# Float24.net
KiCad netlist of a schematic drawn in Altium Designer
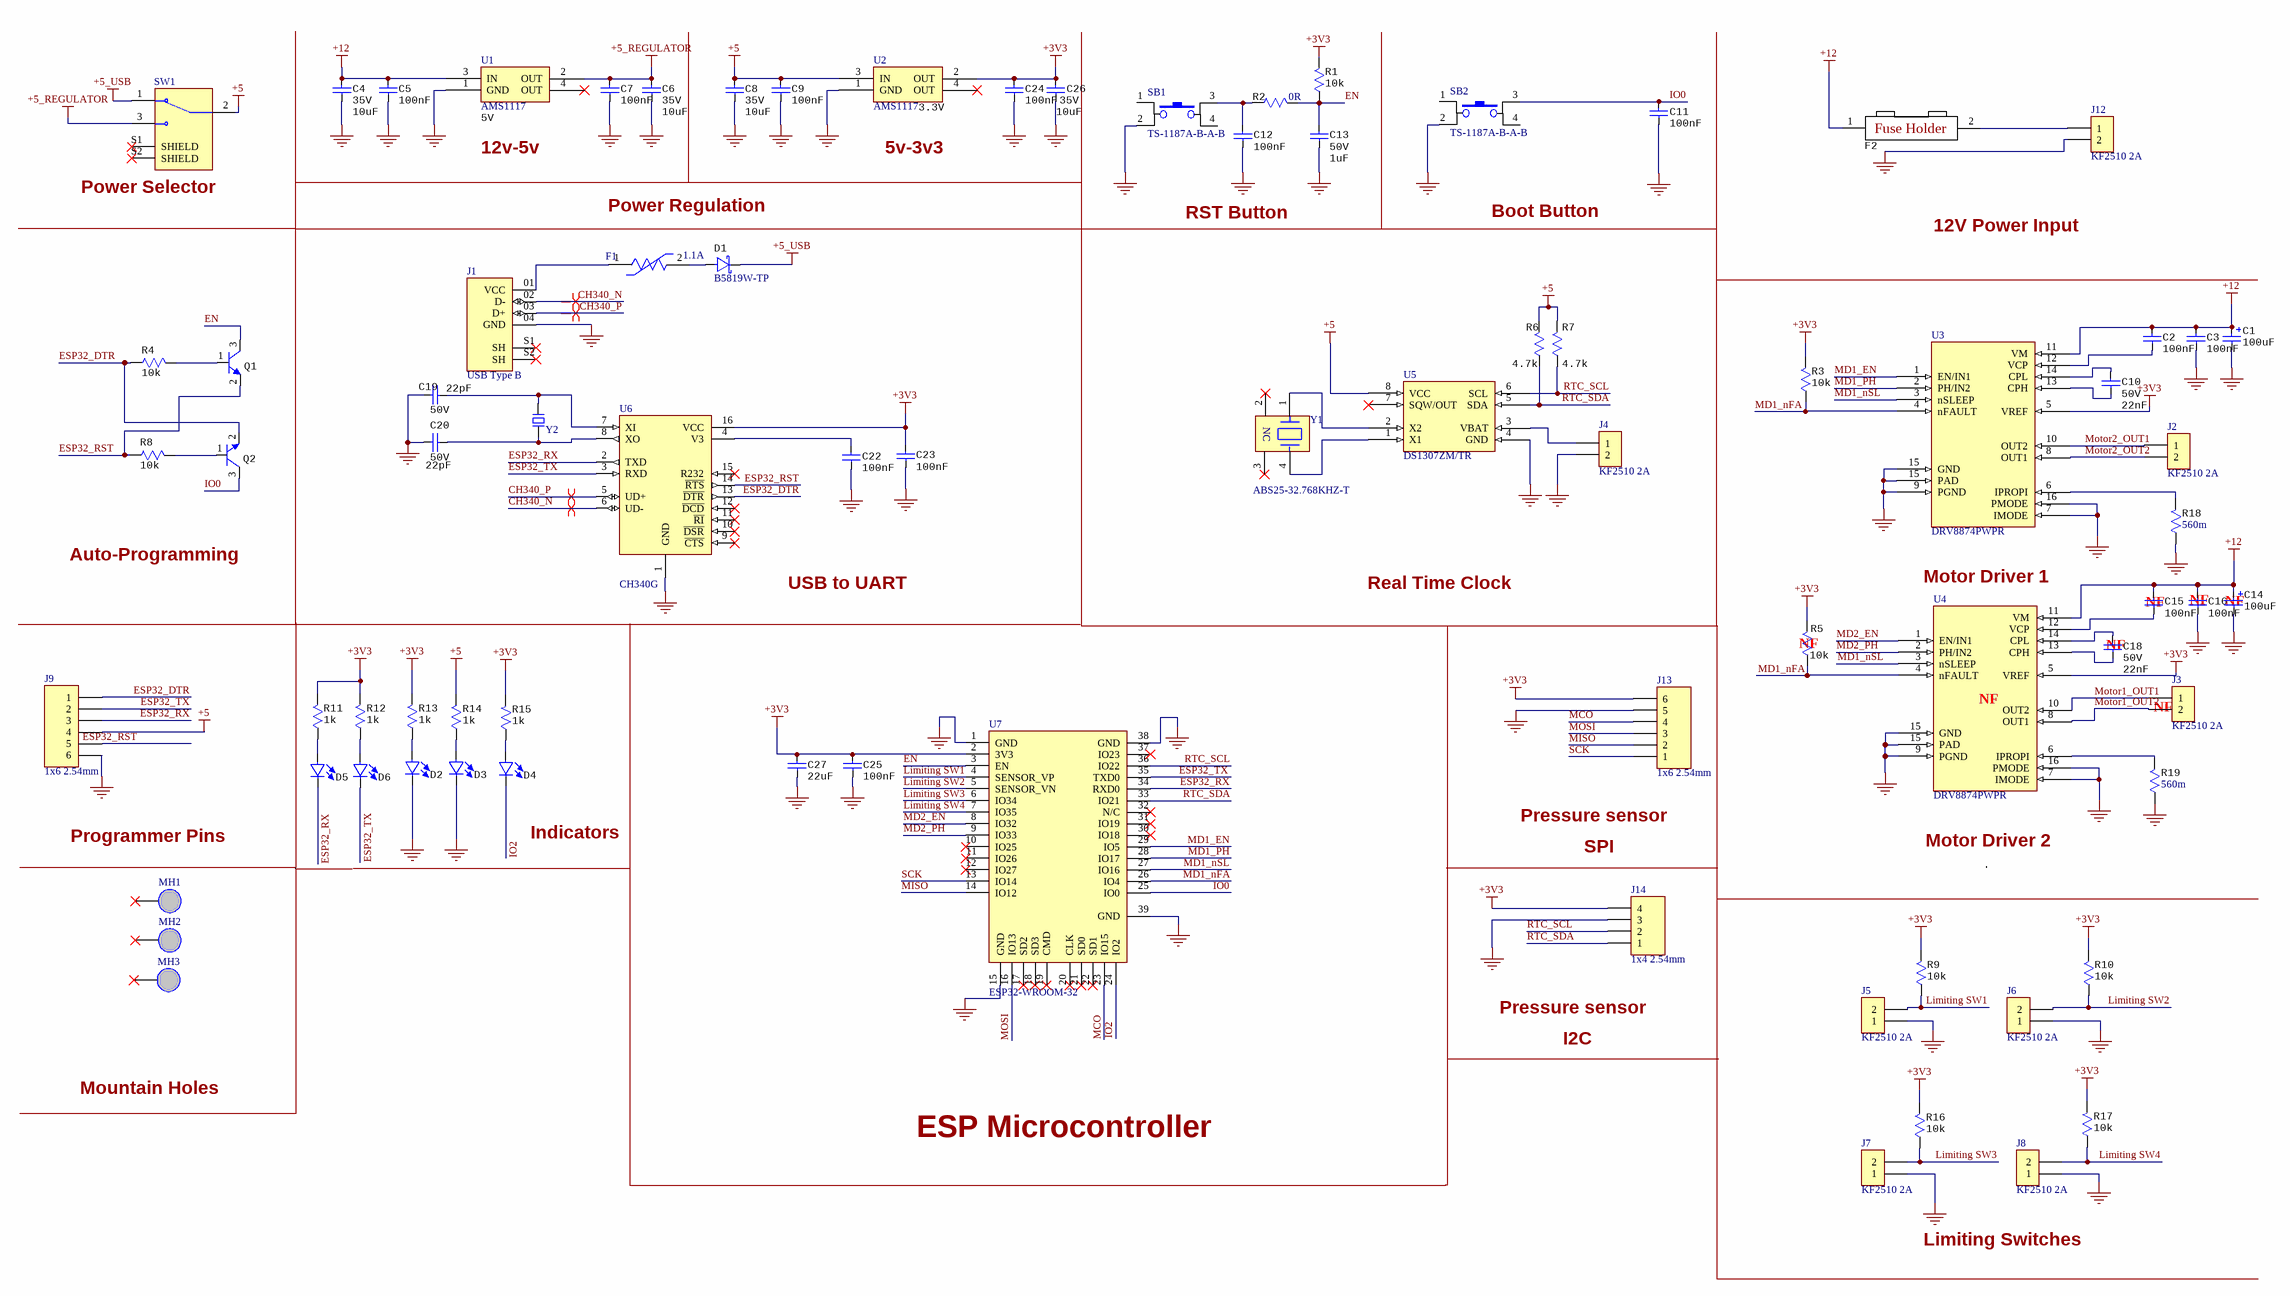
[diagram p0: Float24.SchDoc]

(export (version "E")
  (design (tool "Eeschema 10.0.6"))
  (components
    (comp (ref "C1")
      (value "100uF")
      (footprint "CAP Electrolytic SMD G_10X10.3X10.2(CPOL-EU153CLV-1010)")
      (fields (field (name "MANUFACTURER") "ROQANG") (field (name "MANUFACTURER PART NUMBER") "RT1J101M1010"))
      (libsource (lib "Passive") (part "CAP ELEC 100uF 68V"))
    )
    (comp (ref "C2")
      (value "100nF")
      (footprint "CAP Ceramic SMD 0603")
      (description "0603 0.1 uF 100 V ±10% Tolerance X7R Multilayer Ceramic Capacitor")
      (fields
        (field (name "MANUFACTURER") "Yageo")
        (field (name "MANUFACTURER PART NUMBER") "AC0603KRX7R0BB104")
      )
      (libsource (lib "capacitor") (part "CAP 0603 100nF 100V"))
    )
    (comp (ref "C3")
      (value "100nF")
      (footprint "CAP Ceramic SMD 0603")
      (description "0603 0.1 uF 100 V ±10% Tolerance X7R Multilayer Ceramic Capacitor")
      (fields
        (field (name "MANUFACTURER") "Yageo")
        (field (name "MANUFACTURER PART NUMBER") "AC0603KRX7R0BB104")
      )
      (libsource (lib "capacitor") (part "CAP 0603 100nF 100V"))
    )
    (comp (ref "C4")
      (value "10uF")
      (footprint "CAP Ceramic SMD 0603")
      (description "Cap Ceramic 10uF 35V X5R 20% Pad SMD 0603 85C T/R")
      (fields
        (field (name "MANUFACTURER") "Murata")
        (field (name "MANUFACTURER PART NUMBER") "GRM188R6YA106MA73D")
        (field (name "VOLTAGE") "35V")
      )
      (libsource (lib "Passive") (part "CAP 0603 10uF 35V"))
    )
    (comp (ref "C5")
      (value "100nF")
      (footprint "CAP Ceramic SMD 0603")
      (description "0603 0.1 uF 100 V ±10% Tolerance X7R Multilayer Ceramic Capacitor")
      (fields
        (field (name "MANUFACTURER") "Yageo")
        (field (name "MANUFACTURER PART NUMBER") "AC0603KRX7R0BB104")
      )
      (libsource (lib "capacitor") (part "CAP 0603 100nF 100V"))
    )
    (comp (ref "C6")
      (value "10uF")
      (footprint "CAP Ceramic SMD 0603")
      (description "Cap Ceramic 10uF 35V X5R 20% Pad SMD 0603 85C T/R")
      (fields
        (field (name "MANUFACTURER") "Murata")
        (field (name "MANUFACTURER PART NUMBER") "GRM188R6YA106MA73D")
        (field (name "VOLTAGE") "35V")
      )
      (libsource (lib "Passive") (part "CAP 0603 10uF 35V"))
    )
    (comp (ref "C7")
      (value "100nF")
      (footprint "CAP Ceramic SMD 0603")
      (description "0603 0.1 uF 100 V ±10% Tolerance X7R Multilayer Ceramic Capacitor")
      (fields
        (field (name "MANUFACTURER") "Yageo")
        (field (name "MANUFACTURER PART NUMBER") "AC0603KRX7R0BB104")
      )
      (libsource (lib "capacitor") (part "CAP 0603 100nF 100V"))
    )
    (comp (ref "C8")
      (value "10uF")
      (footprint "CAP Ceramic SMD 0603")
      (description "Cap Ceramic 10uF 35V X5R 20% Pad SMD 0603 85C T/R")
      (fields
        (field (name "MANUFACTURER") "Murata")
        (field (name "MANUFACTURER PART NUMBER") "GRM188R6YA106MA73D")
        (field (name "VOLTAGE") "35V")
      )
      (libsource (lib "Passive") (part "CAP 0603 10uF 35V"))
    )
    (comp (ref "C9")
      (value "100nF")
      (footprint "CAP Ceramic SMD 0603")
      (description "0603 0.1 uF 100 V ±10% Tolerance X7R Multilayer Ceramic Capacitor")
      (fields
        (field (name "MANUFACTURER") "Yageo")
        (field (name "MANUFACTURER PART NUMBER") "AC0603KRX7R0BB104")
      )
      (libsource (lib "capacitor") (part "CAP 0603 100nF 100V"))
    )
    (comp (ref "C10")
      (value "22nF")
      (footprint "CAP Ceramic SMD 0603")
      (description "Ceramic capacitor SMD-0603 22nF /50V X7R# K +-10%, Samsung, RoHS")
      (fields
        (field (name "MANUFACTURER") "Samsung")
        (field (name "MANUFACTURER PART NUMBER") "CL10B223KB8NNNC")
        (field (name "VOLTAGE") "50V")
        (field (name "CAPACITANCE") "22nF")
      )
      (libsource (lib "Passive") (part "CAP 0603 22nF 50V"))
    )
    (comp (ref "C11")
      (value "100nF")
      (footprint "CAP Ceramic SMD 0603")
      (description "0603 0.1 uF 100 V ±10% Tolerance X7R Multilayer Ceramic Capacitor")
      (fields
        (field (name "MANUFACTURER") "Yageo")
        (field (name "MANUFACTURER PART NUMBER") "AC0603KRX7R0BB104")
      )
      (libsource (lib "capacitor") (part "CAP 0603 100nF 100V"))
    )
    (comp (ref "C12")
      (value "100nF")
      (footprint "CAP Ceramic SMD 0603")
      (description "0603 0.1 uF 100 V ±10% Tolerance X7R Multilayer Ceramic Capacitor")
      (fields
        (field (name "MANUFACTURER") "Yageo")
        (field (name "MANUFACTURER PART NUMBER") "AC0603KRX7R0BB104")
      )
      (libsource (lib "capacitor") (part "CAP 0603 100nF 100V"))
    )
    (comp (ref "C13")
      (value "1uF")
      (footprint "CAP Ceramic SMD 0603")
      (description "0603 1 uF 50 V ±10% Tolerance X5R SMT Multilayer Ceramic Capacitor")
      (fields
        (field (name "MANUFACTURER") "Murata")
        (field (name "MANUFACTURER PART NUMBER") "GRM188R61H105KAALD")
        (field (name "VOLTAGE") "50V")
      )
      (libsource (lib "Passive") (part "CAP 0603 1uF 50V"))
    )
    (comp (ref "C14")
      (value "100uF")
      (footprint "CAP Electrolytic SMD G_10X10.3X10.2(CPOL-EU153CLV-1010)")
      (fields (field (name "MANUFACTURER") "ROQANG") (field (name "MANUFACTURER PART NUMBER") "RT1J101M1010"))
      (libsource (lib "Passive") (part "CAP ELEC 100uF 68V"))
    )
    (comp (ref "C15")
      (value "100nF")
      (footprint "CAP Ceramic SMD 0603")
      (description "0603 0.1 uF 100 V ±10% Tolerance X7R Multilayer Ceramic Capacitor")
      (fields
        (field (name "MANUFACTURER") "Yageo")
        (field (name "MANUFACTURER PART NUMBER") "AC0603KRX7R0BB104")
      )
      (libsource (lib "capacitor") (part "CAP 0603 100nF 100V"))
    )
    (comp (ref "C16")
      (value "100nF")
      (footprint "CAP Ceramic SMD 0603")
      (description "0603 0.1 uF 100 V ±10% Tolerance X7R Multilayer Ceramic Capacitor")
      (fields
        (field (name "MANUFACTURER") "Yageo")
        (field (name "MANUFACTURER PART NUMBER") "AC0603KRX7R0BB104")
      )
      (libsource (lib "capacitor") (part "CAP 0603 100nF 100V"))
    )
    (comp (ref "C18")
      (value "22nF")
      (footprint "CAP Ceramic SMD 0603")
      (description "Ceramic capacitor SMD-0603 22nF /50V X7R# K +-10%, Samsung, RoHS")
      (fields
        (field (name "MANUFACTURER") "Samsung")
        (field (name "MANUFACTURER PART NUMBER") "CL10B223KB8NNNC")
        (field (name "VOLTAGE") "50V")
        (field (name "CAPACITANCE") "22nF")
      )
      (libsource (lib "Passive") (part "CAP 0603 22nF 50V"))
    )
    (comp (ref "C19")
      (value "22pF")
      (footprint "CAP Ceramic SMD 0603")
      (description "CAP CER 22PF 50V C0G/NP0 0603")
      (fields
        (field (name "MANUFACTURER") "Samsung")
        (field (name "MANUFACTURER PART NUMBER") "CL10C220JB81PNC")
        (field (name "VOLTAGE") "50V")
      )
      (libsource (lib "Passive") (part "CAP 0603 22pF 50V"))
    )
    (comp (ref "C20")
      (value "22pF")
      (footprint "CAP Ceramic SMD 0603")
      (description "CAP CER 22PF 50V C0G/NP0 0603")
      (fields
        (field (name "MANUFACTURER") "Samsung")
        (field (name "MANUFACTURER PART NUMBER") "CL10C220JB81PNC")
        (field (name "VOLTAGE") "50V")
      )
      (libsource (lib "Passive") (part "CAP 0603 22pF 50V"))
    )
    (comp (ref "C22")
      (value "100nF")
      (footprint "CAP Ceramic SMD 0603")
      (description "0603 0.1 uF 100 V ±10% Tolerance X7R Multilayer Ceramic Capacitor")
      (fields
        (field (name "MANUFACTURER") "Yageo")
        (field (name "MANUFACTURER PART NUMBER") "AC0603KRX7R0BB104")
      )
      (libsource (lib "capacitor") (part "CAP 0603 100nF 100V"))
    )
    (comp (ref "C23")
      (value "100nF")
      (footprint "CAP Ceramic SMD 0603")
      (description "0603 0.1 uF 100 V ±10% Tolerance X7R Multilayer Ceramic Capacitor")
      (fields
        (field (name "MANUFACTURER") "Yageo")
        (field (name "MANUFACTURER PART NUMBER") "AC0603KRX7R0BB104")
      )
      (libsource (lib "capacitor") (part "CAP 0603 100nF 100V"))
    )
    (comp (ref "C24")
      (value "100nF")
      (footprint "CAP Ceramic SMD 0603")
      (description "0603 0.1 uF 100 V ±10% Tolerance X7R Multilayer Ceramic Capacitor")
      (fields
        (field (name "MANUFACTURER") "Yageo")
        (field (name "MANUFACTURER PART NUMBER") "AC0603KRX7R0BB104")
      )
      (libsource (lib "capacitor") (part "CAP 0603 100nF 100V"))
    )
    (comp (ref "C25")
      (value "100nF")
      (footprint "CAP Ceramic SMD 0603")
      (description "0603 0.1 uF 100 V ±10% Tolerance X7R Multilayer Ceramic Capacitor")
      (fields
        (field (name "MANUFACTURER") "Yageo")
        (field (name "MANUFACTURER PART NUMBER") "AC0603KRX7R0BB104")
      )
      (libsource (lib "capacitor") (part "CAP 0603 100nF 100V"))
    )
    (comp (ref "C26")
      (value "10uF")
      (footprint "CAP Ceramic SMD 0603")
      (description "Cap Ceramic 10uF 35V X5R 20% Pad SMD 0603 85C T/R")
      (fields
        (field (name "MANUFACTURER") "Murata")
        (field (name "MANUFACTURER PART NUMBER") "GRM188R6YA106MA73D")
        (field (name "VOLTAGE") "35V")
      )
      (libsource (lib "Passive") (part "CAP 0603 10uF 35V"))
    )
    (comp (ref "C27")
      (value "22uF")
      (footprint "CAP Ceramic SMD 0603")
      (description "16V 22uF 0603 Multilayer Ceramic Capacitors MLCC - SMD/SMT ROHS")
      (fields
        (field (name "MANUFACTURER PART NUMBER") "C0603X5R226M160NT")
        (field (name "MANUFACTURER") "SANYEAR")
        (field (name "CAPACITANCE") "22uF")
      )
      (libsource (lib "Passive") (part "CAP 0603 22uF 16V"))
    )
    (comp (ref "D1")
      (value "~")
      (footprint "Diode Single SMD SOD123")
      (description "40V 600mV@1A 1A SOD-123 Schottky Barrier Diodes (SBD) ROHS")
      (fields (field (name "MANUFACTURER") "MCC") (field (name "MANUFACTURER PART NUMBER") "B5819W-TP"))
      (libsource (lib "diode") (part "B5819W"))
    )
    (comp (ref "D2")
      (value "~")
      (footprint "LED SMD 0805G")
      (description "emerald 0805 Light Emitting Diodes (LED) ROHS")
      (fields
        (field (name "MANUFACTURER") "FOSHAN Nationstar Optoelectronics")
        (field (name "MANUFACTURER PART NUMBER") "NCD0805G1")
      )
      (libsource (lib "diode") (part "LED 0805 Emerald"))
    )
    (comp (ref "D3")
      (value "~")
      (footprint "LED SMD 0805G")
      (description "emerald 0805 Light Emitting Diodes (LED) ROHS")
      (fields
        (field (name "MANUFACTURER") "FOSHAN Nationstar Optoelectronics")
        (field (name "MANUFACTURER PART NUMBER") "NCD0805G1")
      )
      (libsource (lib "diode") (part "LED 0805 Emerald"))
    )
    (comp (ref "D4")
      (value "~")
      (footprint "LED SMD 0805R")
      (description "red 0805 Light Emitting Diodes (LED) ROHS")
      (fields
        (field (name "MANUFACTURER") "FOSHAN Nationstar Optoelectronics")
        (field (name "MANUFACTURER PART NUMBER") "NCD0805R1")
      )
      (libsource (lib "diode") (part "LED 0805 Red"))
    )
    (comp (ref "D5")
      (value "~")
      (footprint "LED SMD 0805B")
      (description "blue 0805 Light Emitting Diodes (LED) ROHS")
      (fields
        (field (name "MANUFACTURER") "FOSHAN Nationstar Optoelectronics")
        (field (name "MANUFACTURER PART NUMBER") "NCD0805B2")
      )
      (libsource (lib "diode") (part "LED 0805 Blue"))
    )
    (comp (ref "D6")
      (value "~")
      (footprint "LED SMD 0805B")
      (description "blue 0805 Light Emitting Diodes (LED) ROHS")
      (fields
        (field (name "MANUFACTURER") "FOSHAN Nationstar Optoelectronics")
        (field (name "MANUFACTURER PART NUMBER") "NCD0805B2")
      )
      (libsource (lib "diode") (part "LED 0805 Blue"))
    )
    (comp (ref "F1")
      (value "1206L110THYR")
      (footprint "FUSE-1206")
      (description "PTC RESET FUSE 8V 1.1A 1206")
      (fields
        (field (name "MANUFACTURER") "Littelfuse")
        (field (name "OCTOPART") "https://octopart.com/1206l110thyr-littelfuse-11800142")
        (field (name "HOLD CURRENT") "1.1A")
      )
      (libsource (lib "Fuse") (part "1206L110THYR"))
    )
    (comp (ref "F2")
      (value "XF-508P-A")
      (footprint "FUSE-TH_L19.8-W7.0_XF-508P-A")
      (description "Plugin Fuse Holders ROHS")
      (fields (field (name "MANUFACTURER") "XFCN"))
      (libsource (lib "Fuse") (part "Fuse Automotive holder"))
    )
    (comp (ref "J1")
      (value "USB Type B")
      (footprint "USB_B_Vertical")
      (fields
        (field (name "MANUFACTURER PART NUMBER") "921-111A1010Y10200")
        (field (name "MANUFACTURER") "Jing Extension of the Electronic Co.")
      )
      (libsource (lib "USB connectors") (part "USB Type B"))
    )
    (comp (ref "J2")
      (value "KF2510 2A")
      (footprint "Connector MOLEX KK-254 KF2510-2")
      (fields (field (name "MANUFACTURER") "CAX") (field (name "MANUFACTURERPARTNUMBER") "2510-2A"))
      (libsource (lib "Signal connectors") (part "KF2510 2A"))
    )
    (comp (ref "J3")
      (value "KF2510 2A")
      (footprint "Connector MOLEX KK-254 KF2510-2")
      (fields (field (name "MANUFACTURER") "CAX") (field (name "MANUFACTURERPARTNUMBER") "2510-2A"))
      (libsource (lib "Signal connectors") (part "KF2510 2A"))
    )
    (comp (ref "J4")
      (value "KF2510 2A")
      (footprint "Connector MOLEX KK-254 KF2510-2")
      (fields (field (name "MANUFACTURER") "CAX") (field (name "MANUFACTURERPARTNUMBER") "2510-2A"))
      (libsource (lib "Signal connectors") (part "KF2510 2A"))
    )
    (comp (ref "J5")
      (value "KF2510 2A")
      (footprint "Connector MOLEX KK-254 KF2510-2")
      (fields (field (name "MANUFACTURER") "CAX") (field (name "MANUFACTURERPARTNUMBER") "2510-2A"))
      (libsource (lib "") (part "KF2510 2A_1"))
    )
    (comp (ref "J6")
      (value "KF2510 2A")
      (footprint "Connector MOLEX KK-254 KF2510-2")
      (fields (field (name "MANUFACTURER") "CAX") (field (name "MANUFACTURERPARTNUMBER") "2510-2A"))
      (libsource (lib "") (part "KF2510 2A_1"))
    )
    (comp (ref "J7")
      (value "KF2510 2A")
      (footprint "Connector MOLEX KK-254 KF2510-2")
      (fields (field (name "MANUFACTURER") "CAX") (field (name "MANUFACTURERPARTNUMBER") "2510-2A"))
      (libsource (lib "") (part "KF2510 2A_1"))
    )
    (comp (ref "J8")
      (value "KF2510 2A")
      (footprint "Connector MOLEX KK-254 KF2510-2")
      (fields (field (name "MANUFACTURER") "CAX") (field (name "MANUFACTURERPARTNUMBER") "2510-2A"))
      (libsource (lib "") (part "KF2510 2A_1"))
    )
    (comp (ref "J9")
      (value "1x6 2.54mm")
      (footprint "Header F 2.54X6")
      (description "Plugin,P=2.54mm Female Headers ROHS")
      (fields (field (name "MANUFACTURER") "CONNYFLY Elec") (field (name "MFR. PART #") "DS1023-1x6SF11"))
      (libsource (lib "Signal connectors") (part "Connector Pinsocket 1x6_1"))
    )
    (comp (ref "J12")
      (value "KF2510 2A")
      (footprint "Connector MOLEX KK-254 KF2510-2")
      (fields (field (name "MANUFACTURER") "CAX") (field (name "MANUFACTURERPARTNUMBER") "2510-2A"))
      (libsource (lib "Signal connectors") (part "KF2510 2A"))
    )
    (comp (ref "J13")
      (value "1x6 2.54mm")
      (footprint "Header F 2.54X6")
      (description "Plugin,P=2.54mm Female Headers ROHS")
      (fields (field (name "MANUFACTURER") "CONNYFLY Elec") (field (name "MFR. PART #") "DS1023-1x6SF11"))
      (libsource (lib "") (part "Connector Pinsocket 1x6_1_1"))
    )
    (comp (ref "J14")
      (value "1x4 2.54mm")
      (footprint "Header F 2.54X4")
      (description "Plugin,P=2.54mm Female Headers ROHS")
      (fields (field (name "MANUFACTURER") "CONNYFLY Elec") (field (name "MFR. PART #") "DS1023-1x4SF11"))
      (libsource (lib "Signal connectors") (part "Connector Pinsocket 1x4"))
    )
    (comp (ref "MH1")
      (value "Mounting Hole 4mm")
      (footprint "Connector Mounting hole TH 4mm")
      (libsource (lib "Bypass, Testpoint and Holes") (part "Mounting Hole 4mm"))
    )
    (comp (ref "MH2")
      (value "Mounting Hole 4mm")
      (footprint "Connector Mounting hole TH 4mm")
      (libsource (lib "Bypass, Testpoint and Holes") (part "Mounting Hole 4mm"))
    )
    (comp (ref "MH3")
      (value "Mounting Hole 4mm")
      (footprint "Connector Mounting hole TH 4mm")
      (libsource (lib "Bypass, Testpoint and Holes") (part "Mounting Hole 4mm"))
    )
    (comp (ref "Q1")
      (value "~")
      (footprint "SOT23")
      (description "NPN Ic=500mA Vceo=45V hfe=100~250 P=225mW SOT-23")
      (fields
        (field (name "MANUFACTURER") "ON Semiconductor")
        (field (name "MANUFACTURER PART NUMBER") "BC817-16LT1G")
      )
      (libsource (lib "Miscellaneous Transistor") (part "BC817"))
    )
    (comp (ref "Q2")
      (value "~")
      (footprint "SOT23")
      (description "NPN Ic=500mA Vceo=45V hfe=100~250 P=225mW SOT-23")
      (fields
        (field (name "MANUFACTURER") "ON Semiconductor")
        (field (name "MANUFACTURER PART NUMBER") "BC817-16LT1G")
      )
      (libsource (lib "Miscellaneous Transistor") (part "BC817"))
    )
    (comp (ref "R1")
      (value "10k")
      (footprint "RES SMD 0603")
      (description "Res Thick Film 0603 10K Ohm 1% 1/10W ±100ppm/°C Molded SMD Punched Carrier T/R")
      (fields
        (field (name "MANUFACTURER") "Panasonic")
        (field (name "MANUFACTURER PART NUMBER") "ERJ-3EKF1002V")
      )
      (libsource (lib "Passive") (part "RES 0603 10k 1%"))
    )
    (comp (ref "R2")
      (value "0R")
      (footprint "RES SMD 0603")
      (description "ERJ Series 0603 0 Ohm 0.05 W Jumper Surface Mount Thick Film Chip Resistor")
      (fields (field (name "TOLERANCE") "1%") (field (name "MANUFACTURER") "Panasonic"))
      (libsource (lib "Passive") (part "RES 0603 0R 1%"))
    )
    (comp (ref "R3")
      (value "10k")
      (footprint "RES SMD 0603")
      (description "Res Thick Film 0603 10K Ohm 1% 1/10W ±100ppm/°C Molded SMD Punched Carrier T/R")
      (fields
        (field (name "MANUFACTURER") "Panasonic")
        (field (name "MANUFACTURER PART NUMBER") "ERJ-3EKF1002V")
      )
      (libsource (lib "Passive") (part "RES 0603 10k 1%"))
    )
    (comp (ref "R4")
      (value "10k")
      (footprint "RES SMD 0603")
      (description "Res Thick Film 0603 10K Ohm 1% 1/10W ±100ppm/°C Molded SMD Punched Carrier T/R")
      (fields
        (field (name "MANUFACTURER") "Panasonic")
        (field (name "MANUFACTURER PART NUMBER") "ERJ-3EKF1002V")
      )
      (libsource (lib "Passive") (part "RES 0603 10k 1%"))
    )
    (comp (ref "R5")
      (value "10k")
      (footprint "RES SMD 0603")
      (description "Res Thick Film 0603 10K Ohm 1% 1/10W ±100ppm/°C Molded SMD Punched Carrier T/R")
      (fields
        (field (name "MANUFACTURER") "Panasonic")
        (field (name "MANUFACTURER PART NUMBER") "ERJ-3EKF1002V")
      )
      (libsource (lib "Passive") (part "RES 0603 10k 1%"))
    )
    (comp (ref "R6")
      (value "4.7k")
      (footprint "RES SMD 0603")
      (description "Res Thin Film 0603 4.7K Ohm 0.1% 1/10W ±25ppm/°C Molded SMD SMD Punched Carrier T/R")
      (fields
        (field (name "MANUFACTURER") "Panasonic")
        (field (name "MANUFACTURER PART NUMBER") "ERA-3AEB472V")
      )
      (libsource (lib "Passive") (part "RES 0603 4.7k 1%"))
    )
    (comp (ref "R7")
      (value "4.7k")
      (footprint "RES SMD 0603")
      (description "Res Thin Film 0603 4.7K Ohm 0.1% 1/10W ±25ppm/°C Molded SMD SMD Punched Carrier T/R")
      (fields
        (field (name "MANUFACTURER") "Panasonic")
        (field (name "MANUFACTURER PART NUMBER") "ERA-3AEB472V")
      )
      (libsource (lib "Passive") (part "RES 0603 4.7k 1%"))
    )
    (comp (ref "R8")
      (value "10k")
      (footprint "RES SMD 0603")
      (description "Res Thick Film 0603 10K Ohm 1% 1/10W ±100ppm/°C Molded SMD Punched Carrier T/R")
      (fields
        (field (name "MANUFACTURER") "Panasonic")
        (field (name "MANUFACTURER PART NUMBER") "ERJ-3EKF1002V")
      )
      (libsource (lib "Passive") (part "RES 0603 10k 1%"))
    )
    (comp (ref "R9")
      (value "10k")
      (footprint "RES SMD 0603")
      (description "Res Thick Film 0603 10K Ohm 1% 1/10W ±100ppm/°C Molded SMD Punched Carrier T/R")
      (fields
        (field (name "MANUFACTURER") "Panasonic")
        (field (name "MANUFACTURER PART NUMBER") "ERJ-3EKF1002V")
      )
      (libsource (lib "Passive") (part "RES 0603 10k 1%"))
    )
    (comp (ref "R10")
      (value "10k")
      (footprint "RES SMD 0603")
      (description "Res Thick Film 0603 10K Ohm 1% 1/10W ±100ppm/°C Molded SMD Punched Carrier T/R")
      (fields
        (field (name "MANUFACTURER") "Panasonic")
        (field (name "MANUFACTURER PART NUMBER") "ERJ-3EKF1002V")
      )
      (libsource (lib "Passive") (part "RES 0603 10k 1%"))
    )
    (comp (ref "R11")
      (value "1k")
      (footprint "RES SMD 0603")
      (description "Res Thick Film 0603 1K Ohm 1% 1/10W ±100ppm/°C Molded SMD Punched Carrier T/R")
      (fields
        (field (name "MANUFACTURER") "Panasonic")
        (field (name "MANUFACTURER PART NUMBER") "ERJ3EKF1001V")
      )
      (libsource (lib "Passive") (part "RES 0603 1k 1%"))
    )
    (comp (ref "R12")
      (value "1k")
      (footprint "RES SMD 0603")
      (description "Res Thick Film 0603 1K Ohm 1% 1/10W ±100ppm/°C Molded SMD Punched Carrier T/R")
      (fields
        (field (name "MANUFACTURER") "Panasonic")
        (field (name "MANUFACTURER PART NUMBER") "ERJ3EKF1001V")
      )
      (libsource (lib "Passive") (part "RES 0603 1k 1%"))
    )
    (comp (ref "R13")
      (value "1k")
      (footprint "RES SMD 0603")
      (description "Res Thick Film 0603 1K Ohm 1% 1/10W ±100ppm/°C Molded SMD Punched Carrier T/R")
      (fields
        (field (name "MANUFACTURER") "Panasonic")
        (field (name "MANUFACTURER PART NUMBER") "ERJ3EKF1001V")
      )
      (libsource (lib "Passive") (part "RES 0603 1k 1%"))
    )
    (comp (ref "R14")
      (value "1k")
      (footprint "RES SMD 0603")
      (description "Res Thick Film 0603 1K Ohm 1% 1/10W ±100ppm/°C Molded SMD Punched Carrier T/R")
      (fields
        (field (name "MANUFACTURER") "Panasonic")
        (field (name "MANUFACTURER PART NUMBER") "ERJ3EKF1001V")
      )
      (libsource (lib "Passive") (part "RES 0603 1k 1%"))
    )
    (comp (ref "R15")
      (value "1k")
      (footprint "RES SMD 0603")
      (description "Res Thick Film 0603 1K Ohm 1% 1/10W ±100ppm/°C Molded SMD Punched Carrier T/R")
      (fields
        (field (name "MANUFACTURER") "Panasonic")
        (field (name "MANUFACTURER PART NUMBER") "ERJ3EKF1001V")
      )
      (libsource (lib "Passive") (part "RES 0603 1k 1%"))
    )
    (comp (ref "R16")
      (value "10k")
      (footprint "RES SMD 0603")
      (description "Res Thick Film 0603 10K Ohm 1% 1/10W ±100ppm/°C Molded SMD Punched Carrier T/R")
      (fields
        (field (name "MANUFACTURER") "Panasonic")
        (field (name "MANUFACTURER PART NUMBER") "ERJ-3EKF1002V")
      )
      (libsource (lib "Passive") (part "RES 0603 10k 1%"))
    )
    (comp (ref "R17")
      (value "10k")
      (footprint "RES SMD 0603")
      (description "Res Thick Film 0603 10K Ohm 1% 1/10W ±100ppm/°C Molded SMD Punched Carrier T/R")
      (fields
        (field (name "MANUFACTURER") "Panasonic")
        (field (name "MANUFACTURER PART NUMBER") "ERJ-3EKF1002V")
      )
      (libsource (lib "Passive") (part "RES 0603 10k 1%"))
    )
    (comp (ref "R18")
      (value "560m")
      (footprint "RES SMD 0603")
      (description "250mW Thick Film Resistors ±5% ±300ppm/℃ 560mΩ 0603 Chip Resistor - Surface Mount ROHS")
      (fields (field (name "TOLERANCE") "5%") (field (name "MANUFACTURER") "Panasonic"))
      (libsource (lib "Passive") (part "RES 0603 560m 5%"))
    )
    (comp (ref "R19")
      (value "560m")
      (footprint "RES SMD 0603")
      (description "250mW Thick Film Resistors ±5% ±300ppm/℃ 560mΩ 0603 Chip Resistor - Surface Mount ROHS")
      (fields (field (name "TOLERANCE") "5%") (field (name "MANUFACTURER") "Panasonic"))
      (libsource (lib "Passive") (part "RES 0603 560m 5%"))
    )
    (comp (ref "SB1")
      (value "TS-1187A-B-A-B")
      (footprint "SW-SMD-4X4X1.5")
      (libsource (lib "Switches") (part "TS-1187A-B-A-B"))
    )
    (comp (ref "SB2")
      (value "TS-1187A-B-A-B")
      (footprint "SW-SMD-4X4X1.5")
      (libsource (lib "Switches") (part "TS-1187A-B-A-B"))
    )
    (comp (ref "SW1")
      (value "~")
      (footprint "SS12 Slide Switch")
      (description "Vertical plug 500mA SPDT 50V 5000次 Plugin Slide Switches ROHS")
      (fields
        (field (name "MANUFACTURER") "SHOU HAN")
        (field (name "MANUFACTURER PART NUMBER") "SS12D07VG4 087")
      )
      (libsource (lib "Switches") (part "SS12D07VG4"))
    )
    (comp (ref "U1")
      (value "AMS1117")
      (footprint "Linear reagulator SMD AMS1117 - duplicate")
      (fields
        (field (name "MANUFACTURER") "Advanced Monolithic Systems")
        (field (name "VOLTAGE OUTPUT") "5V")
      )
      (libsource (lib "Linear regulator") (part "AMS1117_5V"))
    )
    (comp (ref "U2")
      (value "AMS1117")
      (footprint "Linear reagulator SMD AMS1117 - duplicate")
      (fields
        (field (name "MANUFACTURER") "Advanced Monolithic Systems")
        (field (name "VOLTAGE OUTPUT") "3.3V")
      )
      (libsource (lib "Linear regulator") (part "AMS1117"))
    )
    (comp (ref "U3")
      (value "DRV8874PWPR")
      (footprint "DRV8874PWPR")
      (description "40-V, 6-A H-bridge motor driver with integrated current sensing feedback 16-HTSSOP -40 to 125")
      (fields (field (name "MANUFACTURER") "Texas Instruments"))
      (libsource (lib "PMIC") (part "DRV8874PWPR"))
    )
    (comp (ref "U4")
      (value "DRV8874PWPR")
      (footprint "DRV8874PWPR")
      (description "40-V, 6-A H-bridge motor driver with integrated current sensing feedback 16-HTSSOP -40 to 125")
      (fields (field (name "MANUFACTURER") "Texas Instruments"))
      (libsource (lib "PMIC") (part "DRV8874PWPR"))
    )
    (comp (ref "U5")
      (value "DS1307ZM/TR")
      (footprint "SOP-8")
      (description "SOP-8 Real-time Clocks (RTC) ROHS")
      (fields (field (name "MANUFACTURER") "HGSEMI"))
      (libsource (lib "PMIC") (part "DS1307ZM/TR"))
    )
    (comp (ref "U6")
      (value "CH340G")
      (footprint "SOIC127P600X180-16N")
      (description "Transceiver 2Mbps USB 2.0 SOP-16-150mil USB ICs ROHS")
      (fields (field (name "MANUFACTURER") "WCH(Jiangsu Qin Heng)"))
      (libsource (lib "Communictation ICs") (part "CH340G"))
    )
    (comp (ref "U7")
      (value "ESP32-WROOM-32")
      (footprint "ESP32-WROOM-32D")
      (description "Module")
      (fields
        (field (name "MANUFACTURER") "Espressif Systems")
        (field (name "MANUFACTURER PART NUMBER") "ESP32-WROOM-32E-N16")
      )
      (libsource (lib "Miscellaneous MCU") (part "ESP32-WROOM-32"))
    )
    (comp (ref "Y1")
      (value "ABS25-32.768KHZ-T")
      (footprint "Crystal SMD 4-PIN MC-306")
      (description "CRYSTAL 32.7680KHZ 12.5PF SMD")
      (fields (field (name "TOLERANCE") "20ppm"))
      (libsource (lib "Crystal") (part "ABS25-32.768KHZ-T"))
    )
    (comp (ref "Y2")
      (value "X49SD12MSD2SC")
      (footprint "Crystal TH 2-PIN HC-49S")
      (description "HC-49S 12MHz 20pF ±20ppm -20°C~70°C")
      (fields (field (name "MANUFACTURER") "YXC"))
      (libsource (lib "Crystal") (part "X49SD12MSD2SC"))
    )
  )
  (nets
    (net (code "1") (name "+3V3") (class "Default")
      (node (ref "C23") (pin "1") (pinfunction "1_1") (pintype "passive"))
      (node (ref "C24") (pin "1") (pinfunction "1_1") (pintype "passive"))
      (node (ref "C25") (pin "1") (pinfunction "1_1") (pintype "passive"))
      (node (ref "C26") (pin "1") (pinfunction "1_1") (pintype "passive"))
      (node (ref "C27") (pin "1") (pinfunction "1_1") (pintype "passive"))
      (node (ref "J13") (pin "6") (pinfunction "6_6") (pintype "passive"))
      (node (ref "J14") (pin "4") (pinfunction "4_4") (pintype "passive"))
      (node (ref "R1") (pin "2") (pinfunction "2_2") (pintype "passive"))
      (node (ref "R10") (pin "2") (pinfunction "2_2") (pintype "passive"))
      (node (ref "R11") (pin "2") (pinfunction "2_2") (pintype "passive"))
      (node (ref "R12") (pin "2") (pinfunction "2_2") (pintype "passive"))
      (node (ref "R13") (pin "2") (pinfunction "2_2") (pintype "passive"))
      (node (ref "R15") (pin "2") (pinfunction "2_2") (pintype "passive"))
      (node (ref "R16") (pin "2") (pinfunction "2_2") (pintype "passive"))
      (node (ref "R17") (pin "2") (pinfunction "2_2") (pintype "passive"))
      (node (ref "R3") (pin "2") (pinfunction "2_2") (pintype "passive"))
      (node (ref "R5") (pin "2") (pinfunction "2_2") (pintype "passive"))
      (node (ref "R9") (pin "2") (pinfunction "2_2") (pintype "passive"))
      (node (ref "U2") (pin "2") (pinfunction "OUT_2") (pintype "passive"))
      (node (ref "U3") (pin "5") (pinfunction "VREF_5") (pintype "input"))
      (node (ref "U4") (pin "5") (pinfunction "VREF_5") (pintype "input"))
      (node (ref "U6") (pin "16") (pinfunction "VCC_16") (pintype "power_in"))
      (node (ref "U7") (pin "2") (pinfunction "3V3_2") (pintype "passive"))
    )
    (net (code "2") (name "+5") (class "Default")
      (node (ref "C8") (pin "1") (pinfunction "1_1") (pintype "passive"))
      (node (ref "C9") (pin "1") (pinfunction "1_1") (pintype "passive"))
      (node (ref "J9") (pin "4") (pinfunction "4_4") (pintype "passive"))
      (node (ref "R14") (pin "2") (pinfunction "2_2") (pintype "passive"))
      (node (ref "R6") (pin "2") (pinfunction "2_2") (pintype "passive"))
      (node (ref "R7") (pin "2") (pinfunction "2_2") (pintype "passive"))
      (node (ref "SW1") (pin "2") (pinfunction "COM_2_2") (pintype "passive"))
      (node (ref "U2") (pin "3") (pinfunction "IN_3") (pintype "passive"))
      (node (ref "U5") (pin "8") (pinfunction "VCC_8") (pintype "input"))
    )
    (net (code "3") (name "+5_REGULATOR") (class "Default")
      (node (ref "C6") (pin "1") (pinfunction "1_1") (pintype "passive"))
      (node (ref "C7") (pin "1") (pinfunction "1_1") (pintype "passive"))
      (node (ref "SW1") (pin "3") (pinfunction "3_3") (pintype "passive"))
      (node (ref "U1") (pin "2") (pinfunction "OUT_2") (pintype "passive"))
    )
    (net (code "4") (name "+5_USB") (class "Default")
      (node (ref "D1") (pin "2") (pinfunction "2_2") (pintype "passive"))
      (node (ref "SW1") (pin "1") (pinfunction "1_1") (pintype "passive"))
    )
    (net (code "5") (name "+12") (class "Default")
      (node (ref "C1") (pin "1") (pinfunction "1_1") (pintype "passive"))
      (node (ref "C14") (pin "1") (pinfunction "1_1") (pintype "passive"))
      (node (ref "C15") (pin "1") (pinfunction "1_1") (pintype "passive"))
      (node (ref "C16") (pin "1") (pinfunction "1_1") (pintype "passive"))
      (node (ref "C2") (pin "1") (pinfunction "1_1") (pintype "passive"))
      (node (ref "C3") (pin "1") (pinfunction "1_1") (pintype "passive"))
      (node (ref "C4") (pin "1") (pinfunction "1_1") (pintype "passive"))
      (node (ref "C5") (pin "1") (pinfunction "1_1") (pintype "passive"))
      (node (ref "F2") (pin "1") (pinfunction "1_1") (pintype "passive"))
      (node (ref "U1") (pin "3") (pinfunction "IN_3") (pintype "passive"))
      (node (ref "U3") (pin "11") (pinfunction "VM_11") (pintype "input"))
      (node (ref "U4") (pin "11") (pinfunction "VM_11") (pintype "input"))
    )
    (net (code "6") (name "/CH340_N") (class "Default")
      (node (ref "J1") (pin "02") (pinfunction "D-_02") (pintype "bidirectional"))
      (node (ref "U6") (pin "6") (pinfunction "UD-_6") (pintype "bidirectional"))
    )
    (net (code "7") (name "/CH340_P") (class "Default")
      (node (ref "J1") (pin "03") (pinfunction "D+_03") (pintype "bidirectional"))
      (node (ref "U6") (pin "5") (pinfunction "UD+_5") (pintype "bidirectional"))
    )
    (net (code "8") (name "/EN") (class "Default")
      (node (ref "C13") (pin "1") (pinfunction "1_1") (pintype "passive"))
      (node (ref "Q1") (pin "3") (pinfunction "C_3") (pintype "passive"))
      (node (ref "R1") (pin "1") (pinfunction "1_1") (pintype "passive"))
      (node (ref "R2") (pin "2") (pinfunction "2_2") (pintype "passive"))
      (node (ref "U7") (pin "3") (pinfunction "EN_3") (pintype "passive"))
    )
    (net (code "9") (name "/ESP32_DTR") (class "Default")
      (node (ref "J9") (pin "1") (pinfunction "1_1") (pintype "passive"))
      (node (ref "Q2") (pin "2") (pinfunction "E_2") (pintype "passive"))
      (node (ref "R4") (pin "1") (pinfunction "1_1") (pintype "passive"))
      (node (ref "U6") (pin "13") (pinfunction "~{DTR}_13") (pintype "output"))
    )
    (net (code "10") (name "/ESP32_RST") (class "Default")
      (node (ref "J9") (pin "5") (pinfunction "5_5") (pintype "passive"))
      (node (ref "Q1") (pin "2") (pinfunction "E_2") (pintype "passive"))
      (node (ref "R8") (pin "1") (pinfunction "1_1") (pintype "passive"))
      (node (ref "U6") (pin "14") (pinfunction "~{RTS}_14") (pintype "output"))
    )
    (net (code "11") (name "/ESP32_RX") (class "Default")
      (node (ref "D5") (pin "2") (pinfunction "2_2") (pintype "passive"))
      (node (ref "J9") (pin "3") (pinfunction "3_3") (pintype "passive"))
      (node (ref "U6") (pin "2") (pinfunction "TXD_2") (pintype "output"))
      (node (ref "U7") (pin "34") (pinfunction "RXD0_34") (pintype "passive"))
    )
    (net (code "12") (name "/ESP32_TX") (class "Default")
      (node (ref "D6") (pin "2") (pinfunction "2_2") (pintype "passive"))
      (node (ref "J9") (pin "2") (pinfunction "2_2") (pintype "passive"))
      (node (ref "U6") (pin "3") (pinfunction "RXD_3") (pintype "input"))
      (node (ref "U7") (pin "35") (pinfunction "TXD0_35") (pintype "passive"))
    )
    (net (code "13") (name "/IO0") (class "Default")
      (node (ref "C11") (pin "1") (pinfunction "1_1") (pintype "passive"))
      (node (ref "Q2") (pin "3") (pinfunction "C_3") (pintype "passive"))
      (node (ref "SB2") (pin "3") (pinfunction "3_3") (pintype "passive"))
      (node (ref "U7") (pin "25") (pinfunction "IO0_25") (pintype "passive"))
    )
    (net (code "14") (name "/IO2") (class "Default")
      (node (ref "D4") (pin "2") (pinfunction "2_2") (pintype "passive"))
      (node (ref "U7") (pin "24") (pinfunction "IO2_24") (pintype "passive"))
    )
    (net (code "15") (name "/Limiting SW1") (class "Default")
      (node (ref "J5") (pin "2") (pinfunction "2_2") (pintype "passive"))
      (node (ref "R9") (pin "1") (pinfunction "1_1") (pintype "passive"))
      (node (ref "U7") (pin "4") (pinfunction "SENSOR_VP_4") (pintype "passive"))
    )
    (net (code "16") (name "/Limiting SW2") (class "Default")
      (node (ref "J6") (pin "2") (pinfunction "2_2") (pintype "passive"))
      (node (ref "R10") (pin "1") (pinfunction "1_1") (pintype "passive"))
      (node (ref "U7") (pin "5") (pinfunction "SENSOR_VN_5") (pintype "passive"))
    )
    (net (code "17") (name "/Limiting SW3") (class "Default")
      (node (ref "J7") (pin "2") (pinfunction "2_2") (pintype "passive"))
      (node (ref "R16") (pin "1") (pinfunction "1_1") (pintype "passive"))
      (node (ref "U7") (pin "6") (pinfunction "IO34_6") (pintype "passive"))
    )
    (net (code "18") (name "/Limiting SW4") (class "Default")
      (node (ref "J8") (pin "2") (pinfunction "2_2") (pintype "passive"))
      (node (ref "R17") (pin "1") (pinfunction "1_1") (pintype "passive"))
      (node (ref "U7") (pin "7") (pinfunction "IO35_7") (pintype "passive"))
    )
    (net (code "19") (name "/MCO") (class "Default")
      (node (ref "J13") (pin "4") (pinfunction "4_4") (pintype "passive"))
      (node (ref "U7") (pin "23") (pinfunction "IO15_23") (pintype "passive"))
    )
    (net (code "20") (name "/MD1_EN") (class "Default")
      (node (ref "U3") (pin "1") (pinfunction "EN/IN1_1") (pintype "input"))
      (node (ref "U7") (pin "29") (pinfunction "IO5_29") (pintype "passive"))
    )
    (net (code "21") (name "/MD1_PH") (class "Default")
      (node (ref "U3") (pin "2") (pinfunction "PH/IN2_2") (pintype "input"))
      (node (ref "U7") (pin "28") (pinfunction "IO17_28") (pintype "passive"))
    )
    (net (code "22") (name "/MD1_nFA") (class "Default")
      (node (ref "R3") (pin "1") (pinfunction "1_1") (pintype "passive"))
      (node (ref "R5") (pin "1") (pinfunction "1_1") (pintype "passive"))
      (node (ref "U3") (pin "4") (pinfunction "nFAULT_4") (pintype "input"))
      (node (ref "U4") (pin "4") (pinfunction "nFAULT_4") (pintype "input"))
      (node (ref "U7") (pin "26") (pinfunction "IO4_26") (pintype "passive"))
    )
    (net (code "23") (name "/MD1_nSL") (class "Default")
      (node (ref "U3") (pin "3") (pinfunction "nSLEEP_3") (pintype "input"))
      (node (ref "U4") (pin "3") (pinfunction "nSLEEP_3") (pintype "input"))
      (node (ref "U7") (pin "27") (pinfunction "IO16_27") (pintype "passive"))
    )
    (net (code "24") (name "/MD2_EN") (class "Default")
      (node (ref "U4") (pin "1") (pinfunction "EN/IN1_1") (pintype "input"))
      (node (ref "U7") (pin "8") (pinfunction "IO32_8") (pintype "passive"))
    )
    (net (code "25") (name "/MD2_PH") (class "Default")
      (node (ref "U4") (pin "2") (pinfunction "PH/IN2_2") (pintype "input"))
      (node (ref "U7") (pin "9") (pinfunction "IO33_9") (pintype "passive"))
    )
    (net (code "26") (name "/MISO") (class "Default")
      (node (ref "J13") (pin "2") (pinfunction "2_2") (pintype "passive"))
      (node (ref "U7") (pin "14") (pinfunction "IO12_14") (pintype "passive"))
    )
    (net (code "27") (name "/MOSI") (class "Default")
      (node (ref "J13") (pin "3") (pinfunction "3_3") (pintype "passive"))
      (node (ref "U7") (pin "16") (pinfunction "IO13_16") (pintype "passive"))
    )
    (net (code "28") (name "/Motor1_OUT1") (class "Default")
      (node (ref "J3") (pin "1") (pinfunction "1_1") (pintype "passive"))
      (node (ref "U4") (pin "10") (pinfunction "OUT2_10") (pintype "input"))
    )
    (net (code "29") (name "/Motor1_OUT2") (class "Default")
      (node (ref "J3") (pin "2") (pinfunction "2_2") (pintype "passive"))
      (node (ref "U4") (pin "8") (pinfunction "OUT1_8") (pintype "input"))
    )
    (net (code "30") (name "/Motor2_OUT1") (class "Default")
      (node (ref "J2") (pin "1") (pinfunction "1_1") (pintype "passive"))
      (node (ref "U3") (pin "10") (pinfunction "OUT2_10") (pintype "input"))
    )
    (net (code "31") (name "/Motor2_OUT2") (class "Default")
      (node (ref "J2") (pin "2") (pinfunction "2_2") (pintype "passive"))
      (node (ref "U3") (pin "8") (pinfunction "OUT1_8") (pintype "input"))
    )
    (net (code "32") (name "/RTC_SCL") (class "Default")
      (node (ref "J14") (pin "2") (pinfunction "2_2") (pintype "passive"))
      (node (ref "R7") (pin "1") (pinfunction "1_1") (pintype "passive"))
      (node (ref "U5") (pin "6") (pinfunction "SCL_6") (pintype "input"))
      (node (ref "U7") (pin "36") (pinfunction "IO22_36") (pintype "passive"))
    )
    (net (code "33") (name "/RTC_SDA") (class "Default")
      (node (ref "J14") (pin "1") (pinfunction "1_1") (pintype "passive"))
      (node (ref "R6") (pin "1") (pinfunction "1_1") (pintype "passive"))
      (node (ref "U5") (pin "5") (pinfunction "SDA_5") (pintype "input"))
      (node (ref "U7") (pin "33") (pinfunction "IO21_33") (pintype "passive"))
    )
    (net (code "34") (name "/SCK") (class "Default")
      (node (ref "J13") (pin "1") (pinfunction "1_1") (pintype "passive"))
      (node (ref "U7") (pin "13") (pinfunction "IO14_13") (pintype "passive"))
    )
    (net (code "35") (name "GND") (class "Default")
      (node (ref "C1") (pin "2") (pinfunction "2_2") (pintype "passive"))
      (node (ref "C11") (pin "2") (pinfunction "2_2") (pintype "passive"))
      (node (ref "C12") (pin "2") (pinfunction "2_2") (pintype "passive"))
      (node (ref "C13") (pin "2") (pinfunction "2_2") (pintype "passive"))
      (node (ref "C14") (pin "2") (pinfunction "2_2") (pintype "passive"))
      (node (ref "C16") (pin "2") (pinfunction "2_2") (pintype "passive"))
      (node (ref "C19") (pin "1") (pinfunction "1_1") (pintype "passive"))
      (node (ref "C20") (pin "1") (pinfunction "1_1") (pintype "passive"))
      (node (ref "C22") (pin "2") (pinfunction "2_2") (pintype "passive"))
      (node (ref "C23") (pin "2") (pinfunction "2_2") (pintype "passive"))
      (node (ref "C24") (pin "2") (pinfunction "2_2") (pintype "passive"))
      (node (ref "C25") (pin "2") (pinfunction "2_2") (pintype "passive"))
      (node (ref "C26") (pin "2") (pinfunction "2_2") (pintype "passive"))
      (node (ref "C27") (pin "2") (pinfunction "2_2") (pintype "passive"))
      (node (ref "C3") (pin "2") (pinfunction "2_2") (pintype "passive"))
      (node (ref "C4") (pin "2") (pinfunction "2_2") (pintype "passive"))
      (node (ref "C5") (pin "2") (pinfunction "2_2") (pintype "passive"))
      (node (ref "C6") (pin "2") (pinfunction "2_2") (pintype "passive"))
      (node (ref "C7") (pin "2") (pinfunction "2_2") (pintype "passive"))
      (node (ref "C8") (pin "2") (pinfunction "2_2") (pintype "passive"))
      (node (ref "C9") (pin "2") (pinfunction "2_2") (pintype "passive"))
      (node (ref "D2") (pin "2") (pinfunction "2_2") (pintype "passive"))
      (node (ref "D3") (pin "2") (pinfunction "2_2") (pintype "passive"))
      (node (ref "J1") (pin "04") (pinfunction "GND_04") (pintype "power_in"))
      (node (ref "J12") (pin "2") (pinfunction "2_2") (pintype "passive"))
      (node (ref "J13") (pin "5") (pinfunction "5_5") (pintype "passive"))
      (node (ref "J14") (pin "3") (pinfunction "3_3") (pintype "passive"))
      (node (ref "J4") (pin "2") (pinfunction "2_2") (pintype "passive"))
      (node (ref "J5") (pin "1") (pinfunction "1_1") (pintype "passive"))
      (node (ref "J6") (pin "1") (pinfunction "1_1") (pintype "passive"))
      (node (ref "J7") (pin "1") (pinfunction "1_1") (pintype "passive"))
      (node (ref "J8") (pin "1") (pinfunction "1_1") (pintype "passive"))
      (node (ref "J9") (pin "6") (pinfunction "6_6") (pintype "passive"))
      (node (ref "R18") (pin "1") (pinfunction "1_1") (pintype "passive"))
      (node (ref "R19") (pin "1") (pinfunction "1_1") (pintype "passive"))
      (node (ref "SB1") (pin "2") (pinfunction "2_2") (pintype "passive"))
      (node (ref "SB2") (pin "2") (pinfunction "2_2") (pintype "passive"))
      (node (ref "U1") (pin "1") (pinfunction "GND_1") (pintype "passive"))
      (node (ref "U2") (pin "1") (pinfunction "GND_1") (pintype "passive"))
      (node (ref "U3") (pin "15") (pinfunction "PAD_15") (pintype "input"))
      (node (ref "U3") (pin "16") (pinfunction "PMODE_16") (pintype "input"))
      (node (ref "U3") (pin "7") (pinfunction "IMODE_7") (pintype "input"))
      (node (ref "U3") (pin "9") (pinfunction "PGND_9") (pintype "input"))
      (node (ref "U4") (pin "15") (pinfunction "PAD_15") (pintype "input"))
      (node (ref "U4") (pin "16") (pinfunction "PMODE_16") (pintype "input"))
      (node (ref "U4") (pin "7") (pinfunction "IMODE_7") (pintype "input"))
      (node (ref "U4") (pin "9") (pinfunction "PGND_9") (pintype "input"))
      (node (ref "U5") (pin "4") (pinfunction "GND_4") (pintype "input"))
      (node (ref "U6") (pin "1") (pinfunction "GND_1") (pintype "power_in"))
      (node (ref "U7") (pin "1") (pinfunction "GND_1") (pintype "passive"))
      (node (ref "U7") (pin "15") (pinfunction "GND_15") (pintype "passive"))
      (node (ref "U7") (pin "38") (pinfunction "GND_38") (pintype "passive"))
      (node (ref "U7") (pin "39") (pinfunction "GND_39") (pintype "passive"))
    )
    (net (code "36") (name "Net-(C12-Pad1)") (class "Default")
      (node (ref "C12") (pin "1") (pinfunction "1_1") (pintype "passive"))
      (node (ref "R2") (pin "1") (pinfunction "1_1") (pintype "passive"))
      (node (ref "SB1") (pin "3") (pinfunction "3_3") (pintype "passive"))
    )
    (net (code "37") (name "Net-(D1-Pad1)") (class "Default")
      (node (ref "D1") (pin "1") (pinfunction "1_1") (pintype "passive"))
      (node (ref "F1") (pin "2") (pinfunction "2_2") (pintype "passive"))
    )
    (net (code "38") (name "Net-(D2-Pad1)") (class "Default")
      (node (ref "D2") (pin "1") (pinfunction "1_1") (pintype "passive"))
      (node (ref "R13") (pin "1") (pinfunction "1_1") (pintype "passive"))
    )
    (net (code "39") (name "Net-(D3-Pad1)") (class "Default")
      (node (ref "D3") (pin "1") (pinfunction "1_1") (pintype "passive"))
      (node (ref "R14") (pin "1") (pinfunction "1_1") (pintype "passive"))
    )
    (net (code "40") (name "Net-(D4-Pad1)") (class "Default")
      (node (ref "D4") (pin "1") (pinfunction "1_1") (pintype "passive"))
      (node (ref "R15") (pin "1") (pinfunction "1_1") (pintype "passive"))
    )
    (net (code "41") (name "Net-(D5-Pad1)") (class "Default")
      (node (ref "D5") (pin "1") (pinfunction "1_1") (pintype "passive"))
      (node (ref "R11") (pin "1") (pinfunction "1_1") (pintype "passive"))
    )
    (net (code "42") (name "Net-(D6-Pad1)") (class "Default")
      (node (ref "D6") (pin "1") (pinfunction "1_1") (pintype "passive"))
      (node (ref "R12") (pin "1") (pinfunction "1_1") (pintype "passive"))
    )
    (net (code "43") (name "Net-(F2-Pad2)") (class "Default")
      (node (ref "F2") (pin "2") (pinfunction "2_2") (pintype "passive"))
      (node (ref "J12") (pin "1") (pinfunction "1_1") (pintype "passive"))
    )
    (net (code "44") (name "Net-(J1-VCC)") (class "Default")
      (node (ref "F1") (pin "1") (pinfunction "1_1") (pintype "passive"))
      (node (ref "J1") (pin "01") (pinfunction "VCC_01") (pintype "power_in"))
    )
    (net (code "45") (name "Net-(Q1-B)") (class "Default")
      (node (ref "Q1") (pin "1") (pinfunction "B_1") (pintype "passive"))
      (node (ref "R4") (pin "2") (pinfunction "2_2") (pintype "passive"))
    )
    (net (code "46") (name "Net-(Q2-B)") (class "Default")
      (node (ref "Q2") (pin "1") (pinfunction "B_1") (pintype "passive"))
      (node (ref "R8") (pin "2") (pinfunction "2_2") (pintype "passive"))
    )
    (net (code "47") (name "Net-(U3-CPH)") (class "Default")
      (node (ref "C10") (pin "2") (pinfunction "2_2") (pintype "passive"))
      (node (ref "U3") (pin "13") (pinfunction "CPH_13") (pintype "input"))
    )
    (net (code "48") (name "Net-(U3-CPL)") (class "Default")
      (node (ref "C10") (pin "1") (pinfunction "1_1") (pintype "passive"))
      (node (ref "U3") (pin "14") (pinfunction "CPL_14") (pintype "input"))
    )
    (net (code "49") (name "Net-(U3-IPROPI)") (class "Default")
      (node (ref "R18") (pin "2") (pinfunction "2_2") (pintype "passive"))
      (node (ref "U3") (pin "6") (pinfunction "IPROPI_6") (pintype "input"))
    )
    (net (code "50") (name "Net-(U3-VCP)") (class "Default")
      (node (ref "C2") (pin "2") (pinfunction "2_2") (pintype "passive"))
      (node (ref "U3") (pin "12") (pinfunction "VCP_12") (pintype "input"))
    )
    (net (code "51") (name "Net-(U4-CPH)") (class "Default")
      (node (ref "C18") (pin "2") (pinfunction "2_2") (pintype "passive"))
      (node (ref "U4") (pin "13") (pinfunction "CPH_13") (pintype "input"))
    )
    (net (code "52") (name "Net-(U4-CPL)") (class "Default")
      (node (ref "C18") (pin "1") (pinfunction "1_1") (pintype "passive"))
      (node (ref "U4") (pin "14") (pinfunction "CPL_14") (pintype "input"))
    )
    (net (code "53") (name "Net-(U4-IPROPI)") (class "Default")
      (node (ref "R19") (pin "2") (pinfunction "2_2") (pintype "passive"))
      (node (ref "U4") (pin "6") (pinfunction "IPROPI_6") (pintype "input"))
    )
    (net (code "54") (name "Net-(U4-VCP)") (class "Default")
      (node (ref "C15") (pin "2") (pinfunction "2_2") (pintype "passive"))
      (node (ref "U4") (pin "12") (pinfunction "VCP_12") (pintype "input"))
    )
    (net (code "55") (name "Net-(U5-VBAT)") (class "Default")
      (node (ref "J4") (pin "1") (pinfunction "1_1") (pintype "passive"))
      (node (ref "U5") (pin "3") (pinfunction "VBAT_3") (pintype "input"))
    )
    (net (code "56") (name "Net-(U5-X1)") (class "Default")
      (node (ref "U5") (pin "1") (pinfunction "X1_1") (pintype "input"))
      (node (ref "Y1") (pin "4") (pinfunction "4_4") (pintype "passive"))
    )
    (net (code "57") (name "Net-(U5-X2)") (class "Default")
      (node (ref "U5") (pin "2") (pinfunction "X2_2") (pintype "input"))
      (node (ref "Y1") (pin "1") (pinfunction "1_1") (pintype "passive"))
    )
    (net (code "58") (name "Net-(U6-V3)") (class "Default")
      (node (ref "C22") (pin "1") (pinfunction "1_1") (pintype "passive"))
      (node (ref "U6") (pin "4") (pinfunction "V3_4") (pintype "power_in"))
    )
    (net (code "59") (name "Net-(U6-XI)") (class "Default")
      (node (ref "C19") (pin "2") (pinfunction "2_2") (pintype "passive"))
      (node (ref "U6") (pin "7") (pinfunction "XI_7") (pintype "input"))
      (node (ref "Y2") (pin "1") (pinfunction "1_1") (pintype "passive"))
    )
    (net (code "60") (name "Net-(U6-XO)") (class "Default")
      (node (ref "C20") (pin "2") (pinfunction "2_2") (pintype "passive"))
      (node (ref "U6") (pin "8") (pinfunction "XO_8") (pintype "output"))
      (node (ref "Y2") (pin "2") (pinfunction "2_2") (pintype "passive"))
    )
    (net (code "61") (name "unconnected-(J1-SH-PadS1)") (class "Default")
      (node (ref "J1") (pin "S1") (pinfunction "SH_S1") (pintype "passive+no_connect"))
    )
    (net (code "62") (name "unconnected-(J1-SH-PadS2)") (class "Default")
      (node (ref "J1") (pin "S2") (pinfunction "SH_S2") (pintype "passive+no_connect"))
    )
    (net (code "63") (name "unconnected-(MH1-Pad1)") (class "Default")
      (node (ref "MH1") (pin "1") (pinfunction "1_1") (pintype "passive+no_connect"))
    )
    (net (code "64") (name "unconnected-(MH2-Pad1)") (class "Default")
      (node (ref "MH2") (pin "1") (pinfunction "1_1") (pintype "passive+no_connect"))
    )
    (net (code "65") (name "unconnected-(MH3-Pad1)") (class "Default")
      (node (ref "MH3") (pin "1") (pinfunction "1_1") (pintype "passive+no_connect"))
    )
    (net (code "66") (name "unconnected-(SB1-Pad1)") (class "Default")
      (node (ref "SB1") (pin "1") (pinfunction "1_1") (pintype "passive"))
    )
    (net (code "67") (name "unconnected-(SB1-Pad4)") (class "Default")
      (node (ref "SB1") (pin "4") (pinfunction "4_4") (pintype "passive"))
    )
    (net (code "68") (name "unconnected-(SB2-Pad1)") (class "Default")
      (node (ref "SB2") (pin "1") (pinfunction "1_1") (pintype "passive"))
    )
    (net (code "69") (name "unconnected-(SB2-Pad4)") (class "Default")
      (node (ref "SB2") (pin "4") (pinfunction "4_4") (pintype "passive"))
    )
    (net (code "70") (name "unconnected-(SW1-SHIELD-PadS1)") (class "Default")
      (node (ref "SW1") (pin "S1") (pinfunction "SHIELD_S1") (pintype "passive+no_connect"))
    )
    (net (code "71") (name "unconnected-(SW1-SHIELD-PadS2)") (class "Default")
      (node (ref "SW1") (pin "S2") (pinfunction "SHIELD_S2") (pintype "passive+no_connect"))
    )
    (net (code "72") (name "unconnected-(U1-OUT-Pad4)") (class "Default")
      (node (ref "U1") (pin "4") (pinfunction "OUT_4") (pintype "passive+no_connect"))
    )
    (net (code "73") (name "unconnected-(U2-OUT-Pad4)") (class "Default")
      (node (ref "U2") (pin "4") (pinfunction "OUT_4") (pintype "passive+no_connect"))
    )
    (net (code "74") (name "unconnected-(U5-SQW{slash}OUT-Pad7)") (class "Default")
      (node (ref "U5") (pin "7") (pinfunction "SQW/OUT_7") (pintype "input+no_connect"))
    )
    (net (code "75") (name "unconnected-(U6-R232-Pad15)") (class "Default")
      (node (ref "U6") (pin "15") (pinfunction "R232_15") (pintype "input+no_connect"))
    )
    (net (code "76") (name "unconnected-(U6-~{CTS}-Pad9)") (class "Default")
      (node (ref "U6") (pin "9") (pinfunction "~{CTS}_9") (pintype "input+no_connect"))
    )
    (net (code "77") (name "unconnected-(U6-~{DCD}-Pad12)") (class "Default")
      (node (ref "U6") (pin "12") (pinfunction "~{DCD}_12") (pintype "input+no_connect"))
    )
    (net (code "78") (name "unconnected-(U6-~{DSR}-Pad10)") (class "Default")
      (node (ref "U6") (pin "10") (pinfunction "~{DSR}_10") (pintype "input+no_connect"))
    )
    (net (code "79") (name "unconnected-(U6-~{RI}-Pad11)") (class "Default")
      (node (ref "U6") (pin "11") (pinfunction "~{RI}_11") (pintype "input+no_connect"))
    )
    (net (code "80") (name "unconnected-(U7-CLK-Pad20)") (class "Default")
      (node (ref "U7") (pin "20") (pinfunction "CLK_20") (pintype "passive+no_connect"))
    )
    (net (code "81") (name "unconnected-(U7-CMD-Pad19)") (class "Default")
      (node (ref "U7") (pin "19") (pinfunction "CMD_19") (pintype "passive+no_connect"))
    )
    (net (code "82") (name "unconnected-(U7-IO18-Pad30)") (class "Default")
      (node (ref "U7") (pin "30") (pinfunction "IO18_30") (pintype "passive+no_connect"))
    )
    (net (code "83") (name "unconnected-(U7-IO19-Pad31)") (class "Default")
      (node (ref "U7") (pin "31") (pinfunction "IO19_31") (pintype "passive+no_connect"))
    )
    (net (code "84") (name "unconnected-(U7-IO23-Pad37)") (class "Default")
      (node (ref "U7") (pin "37") (pinfunction "IO23_37") (pintype "passive+no_connect"))
    )
    (net (code "85") (name "unconnected-(U7-IO25-Pad10)") (class "Default")
      (node (ref "U7") (pin "10") (pinfunction "IO25_10") (pintype "passive+no_connect"))
    )
    (net (code "86") (name "unconnected-(U7-IO26-Pad11)") (class "Default")
      (node (ref "U7") (pin "11") (pinfunction "IO26_11") (pintype "passive+no_connect"))
    )
    (net (code "87") (name "unconnected-(U7-IO27-Pad12)") (class "Default")
      (node (ref "U7") (pin "12") (pinfunction "IO27_12") (pintype "passive+no_connect"))
    )
    (net (code "88") (name "unconnected-(U7-N{slash}C-Pad32)") (class "Default")
      (node (ref "U7") (pin "32") (pinfunction "N/C_32") (pintype "passive+no_connect"))
    )
    (net (code "89") (name "unconnected-(U7-SD0-Pad21)") (class "Default")
      (node (ref "U7") (pin "21") (pinfunction "SD0_21") (pintype "passive+no_connect"))
    )
    (net (code "90") (name "unconnected-(U7-SD1-Pad22)") (class "Default")
      (node (ref "U7") (pin "22") (pinfunction "SD1_22") (pintype "passive+no_connect"))
    )
    (net (code "91") (name "unconnected-(U7-SD2-Pad17)") (class "Default")
      (node (ref "U7") (pin "17") (pinfunction "SD2_17") (pintype "passive+no_connect"))
    )
    (net (code "92") (name "unconnected-(U7-SD3-Pad18)") (class "Default")
      (node (ref "U7") (pin "18") (pinfunction "SD3_18") (pintype "passive+no_connect"))
    )
    (net (code "93") (name "unconnected-(Y1-NC-Pad2)") (class "Default")
      (node (ref "Y1") (pin "2") (pinfunction "NC_2") (pintype "passive+no_connect"))
    )
    (net (code "94") (name "unconnected-(Y1-NC-Pad3)") (class "Default")
      (node (ref "Y1") (pin "3") (pinfunction "NC_3") (pintype "passive+no_connect"))
    )
  )
)
